# DRV8839.net
KiCad netlist of a schematic drawn in EAGLE
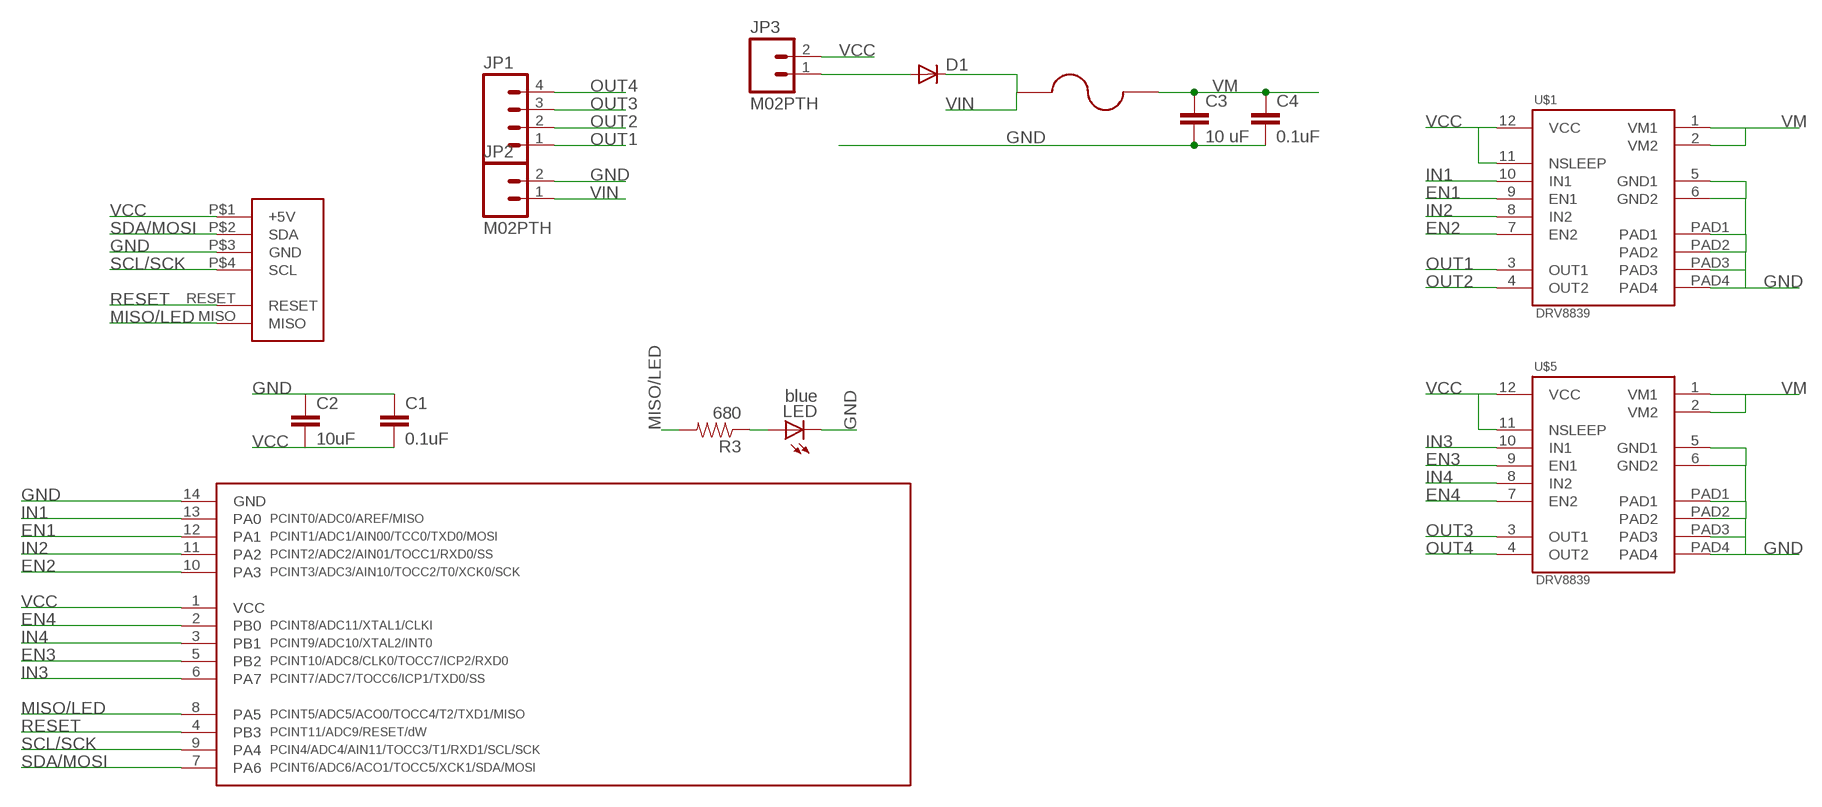
[diagram p0: schematic, sheet 1]

(export (version "E")
  (design (tool "Eeschema 10.0.6"))
  (components
    (comp (ref "C1")
      (value "0.1uF")
      (footprint "eagle-import:0805")
      (libsource (lib "eagle-import") (part "CAP0805"))
    )
    (comp (ref "C2")
      (value "10uF")
      (footprint "eagle-import:0805")
      (libsource (lib "eagle-import") (part "CAP0805"))
    )
    (comp (ref "C3")
      (value "10 uF")
      (footprint "eagle-import:0805")
      (libsource (lib "eagle-import") (part "CAP0805"))
    )
    (comp (ref "C4")
      (value "0.1uF")
      (footprint "eagle-import:0805")
      (libsource (lib "eagle-import") (part "CAP0805"))
    )
    (comp (ref "D1")
      (value "DIODESMC/DO-214AB")
      (footprint "eagle-import:SMC")
      (libsource (lib "eagle-import") (part "DIODESMC/DO-214AB"))
    )
    (comp (ref "JP1")
      (value "M04PTH")
      (footprint "eagle-import:1X04")
      (libsource (lib "eagle-import") (part "M04PTH"))
    )
    (comp (ref "JP2")
      (value "M02PTH")
      (footprint "eagle-import:1X02")
      (libsource (lib "eagle-import") (part "M02PTH"))
    )
    (comp (ref "JP3")
      (value "M02PTH")
      (footprint "eagle-import:1X02")
      (libsource (lib "eagle-import") (part "M02PTH"))
    )
    (comp (ref "LED")
      (value "blue")
      (footprint "eagle-import:CHIPLED_1206")
      (libsource (lib "eagle-import") (part "LEDCHIPLED_1206"))
    )
    (comp (ref "R3")
      (value "680")
      (footprint "eagle-import:0805")
      (libsource (lib "eagle-import") (part "RESISTOR0805-RES"))
    )
    (comp (ref "U$1")
      (value "DRV8839")
      (footprint "eagle-import:WSON-POWERPAD-12")
      (libsource (lib "eagle-import") (part "DRV8839"))
    )
    (comp (ref "U$2")
      (value "FUSE")
      (footprint "eagle-import:1812")
      (libsource (lib "eagle-import") (part "FUSE"))
    )
    (comp (ref "U$3")
      (value "TINY841")
      (footprint "eagle-import:SOIC14")
      (libsource (lib "eagle-import") (part "TINY841"))
    )
    (comp (ref "U$4")
      (value "FOOTPRINT")
      (footprint "eagle-import:FOOTPRINT")
      (libsource (lib "eagle-import") (part "FOOTPRINT"))
    )
    (comp (ref "U$5")
      (value "DRV8839")
      (footprint "eagle-import:WSON-POWERPAD-12")
      (libsource (lib "eagle-import") (part "DRV8839"))
    )
  )
  (nets
    (net (code "1") (name "/EN1") (class "Default")
      (node (ref "U$1") (pin "9") (pinfunction "EN1_9") (pintype "bidirectional"))
      (node (ref "U$3") (pin "12") (pinfunction "PA1_12") (pintype "bidirectional"))
    )
    (net (code "2") (name "/EN2") (class "Default")
      (node (ref "U$1") (pin "7") (pinfunction "EN2_7") (pintype "bidirectional"))
      (node (ref "U$3") (pin "10") (pinfunction "PA3_10") (pintype "bidirectional"))
    )
    (net (code "3") (name "/EN3") (class "Default")
      (node (ref "U$3") (pin "5") (pinfunction "PB2_5") (pintype "bidirectional"))
      (node (ref "U$5") (pin "9") (pinfunction "EN1_9") (pintype "bidirectional"))
    )
    (net (code "4") (name "/EN4") (class "Default")
      (node (ref "U$3") (pin "2") (pinfunction "PB0_2") (pintype "bidirectional"))
      (node (ref "U$5") (pin "7") (pinfunction "EN2_7") (pintype "bidirectional"))
    )
    (net (code "5") (name "/GND") (class "Default")
      (node (ref "C1") (pin "1") (pinfunction "1_1") (pintype "passive"))
      (node (ref "C2") (pin "1") (pinfunction "1_1") (pintype "passive"))
      (node (ref "C3") (pin "2") (pinfunction "2_2") (pintype "passive"))
      (node (ref "C4") (pin "2") (pinfunction "2_2") (pintype "passive"))
      (node (ref "JP2") (pin "2") (pinfunction "2_2") (pintype "passive"))
      (node (ref "LED") (pin "C") (pinfunction "C_C") (pintype "passive"))
      (node (ref "U$1") (pin "5") (pinfunction "GND1_5") (pintype "bidirectional"))
      (node (ref "U$1") (pin "6") (pinfunction "GND2_6") (pintype "bidirectional"))
      (node (ref "U$1") (pin "PAD1") (pinfunction "PAD1_PAD1") (pintype "bidirectional"))
      (node (ref "U$1") (pin "PAD2") (pinfunction "PAD2_PAD2") (pintype "bidirectional"))
      (node (ref "U$1") (pin "PAD3") (pinfunction "PAD3_PAD3") (pintype "bidirectional"))
      (node (ref "U$1") (pin "PAD4") (pinfunction "PAD4_PAD4") (pintype "bidirectional"))
      (node (ref "U$3") (pin "14") (pinfunction "GND_14") (pintype "bidirectional"))
      (node (ref "U$4") (pin "P$3") (pinfunction "GND_P$3") (pintype "power_in"))
      (node (ref "U$5") (pin "5") (pinfunction "GND1_5") (pintype "bidirectional"))
      (node (ref "U$5") (pin "6") (pinfunction "GND2_6") (pintype "bidirectional"))
      (node (ref "U$5") (pin "PAD1") (pinfunction "PAD1_PAD1") (pintype "bidirectional"))
      (node (ref "U$5") (pin "PAD2") (pinfunction "PAD2_PAD2") (pintype "bidirectional"))
      (node (ref "U$5") (pin "PAD3") (pinfunction "PAD3_PAD3") (pintype "bidirectional"))
      (node (ref "U$5") (pin "PAD4") (pinfunction "PAD4_PAD4") (pintype "bidirectional"))
    )
    (net (code "6") (name "/IN1") (class "Default")
      (node (ref "U$1") (pin "10") (pinfunction "IN1_10") (pintype "bidirectional"))
      (node (ref "U$3") (pin "13") (pinfunction "PA0_13") (pintype "bidirectional"))
    )
    (net (code "7") (name "/IN2") (class "Default")
      (node (ref "U$1") (pin "8") (pinfunction "IN2_8") (pintype "bidirectional"))
      (node (ref "U$3") (pin "11") (pinfunction "PA2_11") (pintype "bidirectional"))
    )
    (net (code "8") (name "/IN3") (class "Default")
      (node (ref "U$3") (pin "6") (pinfunction "PA7_6") (pintype "bidirectional"))
      (node (ref "U$5") (pin "10") (pinfunction "IN1_10") (pintype "bidirectional"))
    )
    (net (code "9") (name "/IN4") (class "Default")
      (node (ref "U$3") (pin "3") (pinfunction "PB1_3") (pintype "bidirectional"))
      (node (ref "U$5") (pin "8") (pinfunction "IN2_8") (pintype "bidirectional"))
    )
    (net (code "10") (name "/MISO{slash}LED") (class "Default")
      (node (ref "R3") (pin "2") (pinfunction "2_2") (pintype "passive"))
      (node (ref "U$3") (pin "8") (pinfunction "PA5_8") (pintype "bidirectional"))
      (node (ref "U$4") (pin "MISO") (pinfunction "MISO_MISO") (pintype "bidirectional"))
    )
    (net (code "11") (name "/OUT1") (class "Default")
      (node (ref "JP1") (pin "1") (pinfunction "1_1") (pintype "passive"))
      (node (ref "U$1") (pin "3") (pinfunction "OUT1_3") (pintype "bidirectional"))
    )
    (net (code "12") (name "/OUT2") (class "Default")
      (node (ref "JP1") (pin "2") (pinfunction "2_2") (pintype "passive"))
      (node (ref "U$1") (pin "4") (pinfunction "OUT2_4") (pintype "bidirectional"))
    )
    (net (code "13") (name "/OUT3") (class "Default")
      (node (ref "JP1") (pin "3") (pinfunction "3_3") (pintype "passive"))
      (node (ref "U$5") (pin "3") (pinfunction "OUT1_3") (pintype "bidirectional"))
    )
    (net (code "14") (name "/OUT4") (class "Default")
      (node (ref "JP1") (pin "4") (pinfunction "4_4") (pintype "passive"))
      (node (ref "U$5") (pin "4") (pinfunction "OUT2_4") (pintype "bidirectional"))
    )
    (net (code "15") (name "/RESET") (class "Default")
      (node (ref "U$3") (pin "4") (pinfunction "PB3_4") (pintype "bidirectional"))
      (node (ref "U$4") (pin "RESET") (pinfunction "RESET_RESET") (pintype "bidirectional"))
    )
    (net (code "16") (name "/SCL{slash}SCK") (class "Default")
      (node (ref "U$3") (pin "9") (pinfunction "PA4_9") (pintype "bidirectional"))
      (node (ref "U$4") (pin "P$4") (pinfunction "SCL_P$4") (pintype "bidirectional"))
    )
    (net (code "17") (name "/SDA{slash}MOSI") (class "Default")
      (node (ref "U$3") (pin "7") (pinfunction "PA6_7") (pintype "bidirectional"))
      (node (ref "U$4") (pin "P$2") (pinfunction "SDA_P$2") (pintype "bidirectional"))
    )
    (net (code "18") (name "/VCC") (class "Default")
      (node (ref "C1") (pin "2") (pinfunction "2_2") (pintype "passive"))
      (node (ref "C2") (pin "2") (pinfunction "2_2") (pintype "passive"))
      (node (ref "JP3") (pin "2") (pinfunction "2_2") (pintype "passive"))
      (node (ref "U$1") (pin "11") (pinfunction "NSLEEP_11") (pintype "bidirectional"))
      (node (ref "U$1") (pin "12") (pinfunction "VCC_12") (pintype "bidirectional"))
      (node (ref "U$3") (pin "1") (pinfunction "VCC_1") (pintype "bidirectional"))
      (node (ref "U$4") (pin "P$1") (pinfunction "+5V_P$1") (pintype "power_in"))
      (node (ref "U$5") (pin "11") (pinfunction "NSLEEP_11") (pintype "bidirectional"))
      (node (ref "U$5") (pin "12") (pinfunction "VCC_12") (pintype "bidirectional"))
    )
    (net (code "19") (name "/VIN") (class "Default")
      (node (ref "D1") (pin "C") (pinfunction "C_C") (pintype "passive"))
      (node (ref "JP2") (pin "1") (pinfunction "1_1") (pintype "passive"))
      (node (ref "U$2") (pin "P$1") (pinfunction "1_P$1") (pintype "bidirectional"))
    )
    (net (code "20") (name "/VM") (class "Default")
      (node (ref "C3") (pin "1") (pinfunction "1_1") (pintype "passive"))
      (node (ref "C4") (pin "1") (pinfunction "1_1") (pintype "passive"))
      (node (ref "U$1") (pin "1") (pinfunction "VM1_1") (pintype "bidirectional"))
      (node (ref "U$1") (pin "2") (pinfunction "VM2_2") (pintype "bidirectional"))
      (node (ref "U$2") (pin "P$2") (pinfunction "2_P$2") (pintype "bidirectional"))
      (node (ref "U$5") (pin "1") (pinfunction "VM1_1") (pintype "bidirectional"))
      (node (ref "U$5") (pin "2") (pinfunction "VM2_2") (pintype "bidirectional"))
    )
    (net (code "21") (name "Net-(D1-PadA)") (class "Default")
      (node (ref "D1") (pin "A") (pinfunction "A_A") (pintype "passive"))
      (node (ref "JP3") (pin "1") (pinfunction "1_1") (pintype "passive"))
    )
    (net (code "22") (name "Net-(LED-PadA)") (class "Default")
      (node (ref "LED") (pin "A") (pinfunction "A_A") (pintype "passive"))
      (node (ref "R3") (pin "1") (pinfunction "1_1") (pintype "passive"))
    )
  )
)
